# LED-mini-SHIM.net
KiCad netlist of a schematic drawn in EAGLE
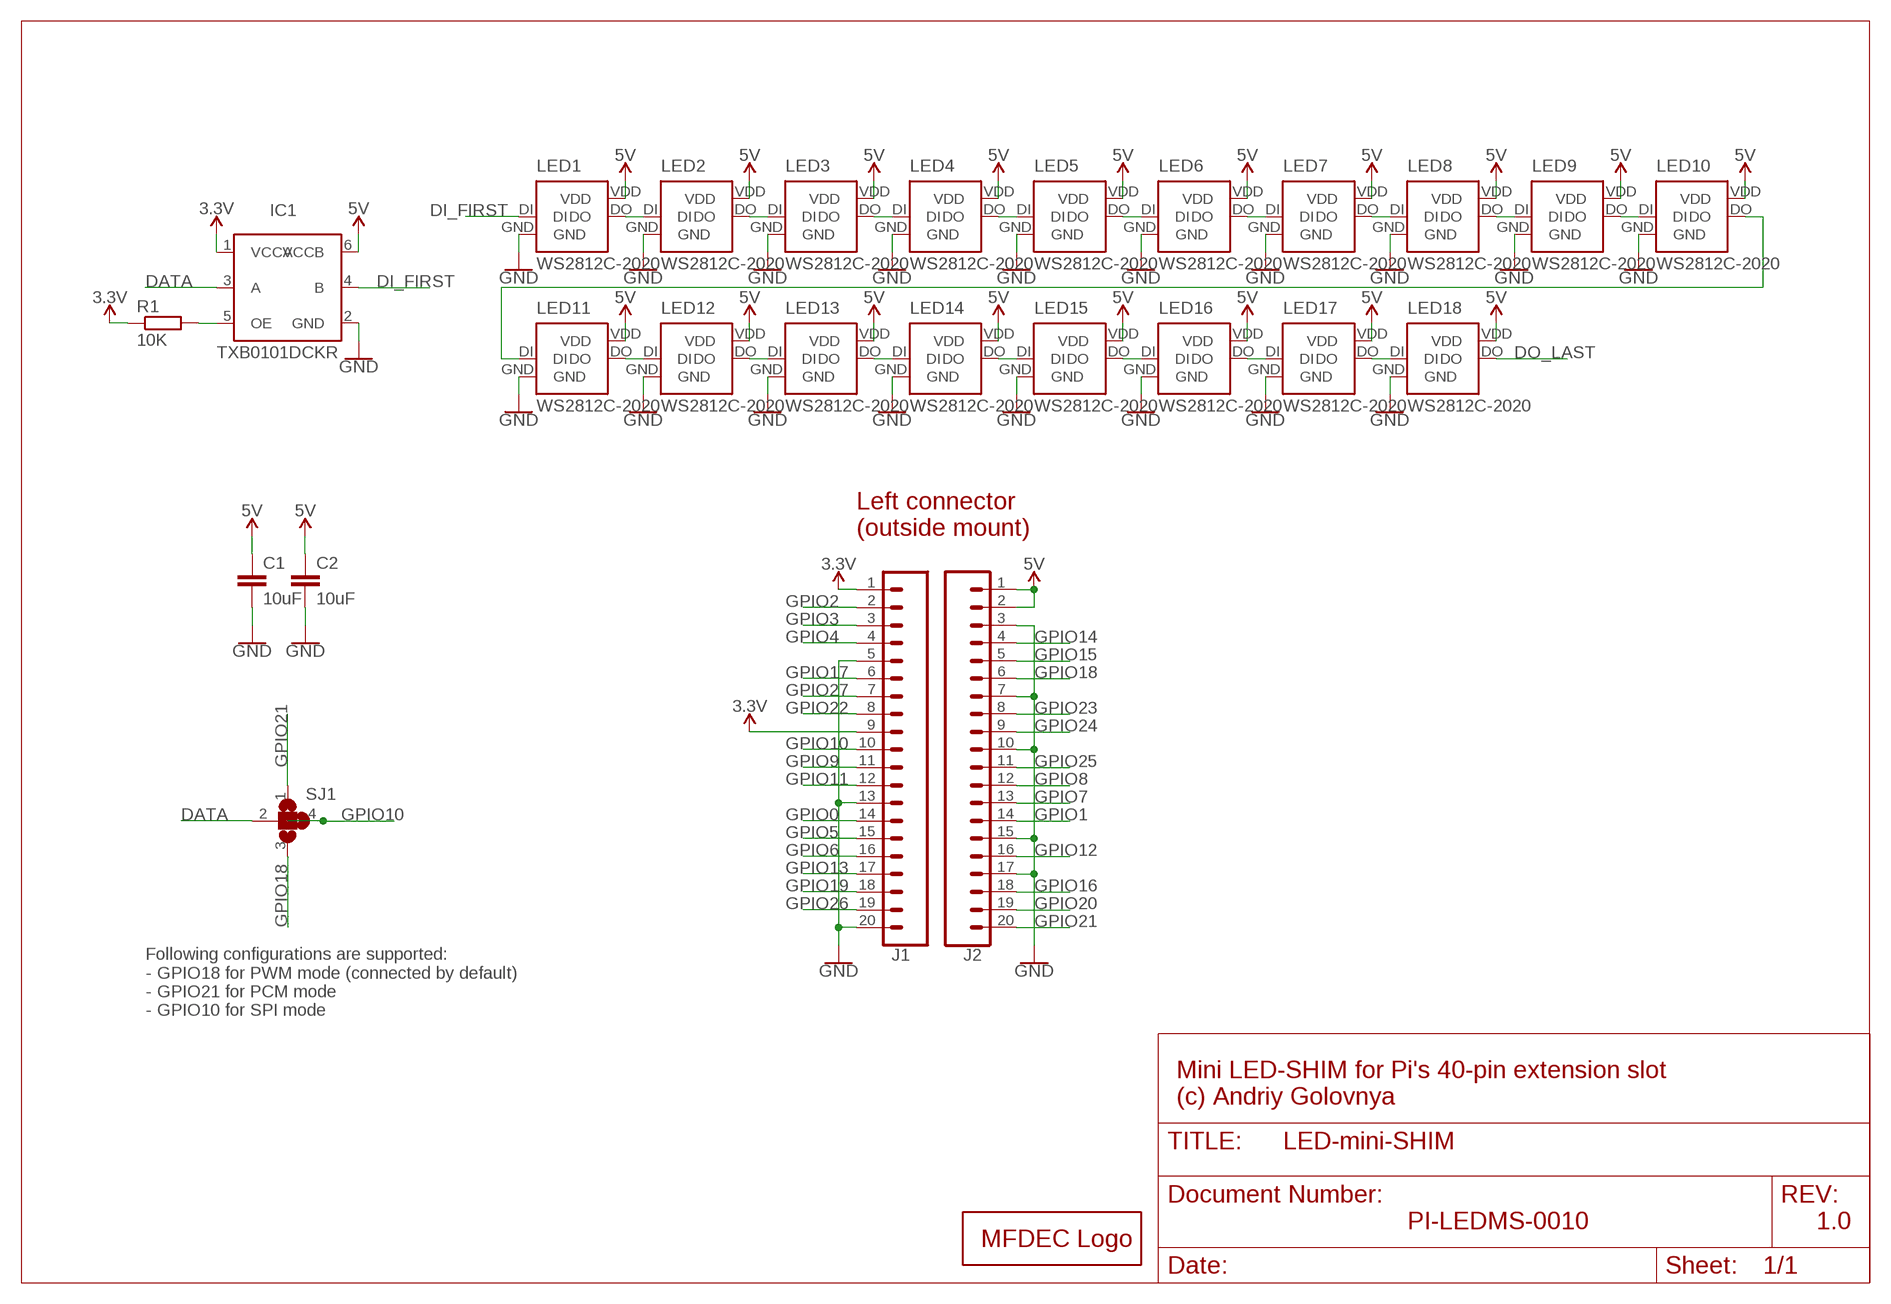
[diagram p0: schematic, sheet 1]

(export (version "E")
  (design (tool "Eeschema 10.0.6"))
  (components
    (comp (ref "C1")
      (value "10uF")
      (footprint "eagle-import:C0805")
      (libsource (lib "eagle-import") (part "C-EUC0805"))
    )
    (comp (ref "C2")
      (value "10uF")
      (footprint "eagle-import:C0805")
      (libsource (lib "eagle-import") (part "C-EUC0805"))
    )
    (comp (ref "IC1")
      (value "TXB0101DCKR")
      (footprint "eagle-import:SOT65P210X110-6N")
      (libsource (lib "eagle-import") (part "TXB0101DCKR"))
    )
    (comp (ref "J1")
      (value "CONN_20LOCK")
      (footprint "eagle-import:1X20_LOCK")
      (libsource (lib "eagle-import") (part "CONN_20LOCK"))
    )
    (comp (ref "J2")
      (value "CONN_20LOCK")
      (footprint "eagle-import:1X20_LOCK")
      (libsource (lib "eagle-import") (part "CONN_20LOCK"))
    )
    (comp (ref "LED1")
      (value "WS2812C-2020")
      (footprint "eagle-import:WS2812X-2020")
      (libsource (lib "eagle-import") (part "WS2812C-2020"))
    )
    (comp (ref "LED2")
      (value "WS2812C-2020")
      (footprint "eagle-import:WS2812X-2020")
      (libsource (lib "eagle-import") (part "WS2812C-2020"))
    )
    (comp (ref "LED3")
      (value "WS2812C-2020")
      (footprint "eagle-import:WS2812X-2020")
      (libsource (lib "eagle-import") (part "WS2812C-2020"))
    )
    (comp (ref "LED4")
      (value "WS2812C-2020")
      (footprint "eagle-import:WS2812X-2020")
      (libsource (lib "eagle-import") (part "WS2812C-2020"))
    )
    (comp (ref "LED5")
      (value "WS2812C-2020")
      (footprint "eagle-import:WS2812X-2020")
      (libsource (lib "eagle-import") (part "WS2812C-2020"))
    )
    (comp (ref "LED6")
      (value "WS2812C-2020")
      (footprint "eagle-import:WS2812X-2020")
      (libsource (lib "eagle-import") (part "WS2812C-2020"))
    )
    (comp (ref "LED7")
      (value "WS2812C-2020")
      (footprint "eagle-import:WS2812X-2020")
      (libsource (lib "eagle-import") (part "WS2812C-2020"))
    )
    (comp (ref "LED8")
      (value "WS2812C-2020")
      (footprint "eagle-import:WS2812X-2020")
      (libsource (lib "eagle-import") (part "WS2812C-2020"))
    )
    (comp (ref "LED9")
      (value "WS2812C-2020")
      (footprint "eagle-import:WS2812X-2020")
      (libsource (lib "eagle-import") (part "WS2812C-2020"))
    )
    (comp (ref "LED10")
      (value "WS2812C-2020")
      (footprint "eagle-import:WS2812X-2020")
      (libsource (lib "eagle-import") (part "WS2812C-2020"))
    )
    (comp (ref "LED11")
      (value "WS2812C-2020")
      (footprint "eagle-import:WS2812X-2020")
      (libsource (lib "eagle-import") (part "WS2812C-2020"))
    )
    (comp (ref "LED12")
      (value "WS2812C-2020")
      (footprint "eagle-import:WS2812X-2020")
      (libsource (lib "eagle-import") (part "WS2812C-2020"))
    )
    (comp (ref "LED13")
      (value "WS2812C-2020")
      (footprint "eagle-import:WS2812X-2020")
      (libsource (lib "eagle-import") (part "WS2812C-2020"))
    )
    (comp (ref "LED14")
      (value "WS2812C-2020")
      (footprint "eagle-import:WS2812X-2020")
      (libsource (lib "eagle-import") (part "WS2812C-2020"))
    )
    (comp (ref "LED15")
      (value "WS2812C-2020")
      (footprint "eagle-import:WS2812X-2020")
      (libsource (lib "eagle-import") (part "WS2812C-2020"))
    )
    (comp (ref "LED16")
      (value "WS2812C-2020")
      (footprint "eagle-import:WS2812X-2020")
      (libsource (lib "eagle-import") (part "WS2812C-2020"))
    )
    (comp (ref "LED17")
      (value "WS2812C-2020")
      (footprint "eagle-import:WS2812X-2020")
      (libsource (lib "eagle-import") (part "WS2812C-2020"))
    )
    (comp (ref "LED18")
      (value "WS2812C-2020")
      (footprint "eagle-import:WS2812X-2020")
      (libsource (lib "eagle-import") (part "WS2812C-2020"))
    )
    (comp (ref "LOGO1")
      (value "MFDECLOGO_L_10MM")
      (footprint "eagle-import:MFDEC_L_10MM")
      (libsource (lib "eagle-import") (part "MFDECLOGO_L_10MM"))
    )
    (comp (ref "R1")
      (value "10K")
      (footprint "eagle-import:R0402")
      (libsource (lib "eagle-import") (part "R-EU_R0402"))
    )
    (comp (ref "SJ1")
      (value "SJ3")
      (footprint "eagle-import:SJ_3")
      (libsource (lib "eagle-import") (part "SJ3"))
    )
  )
  (nets
    (net (code "1") (name "/DATA") (class "Default")
      (node (ref "IC1") (pin "3") (pinfunction "A_3") (pintype "bidirectional"))
      (node (ref "SJ1") (pin "2") (pinfunction "2_2") (pintype "passive"))
    )
    (net (code "2") (name "/DI_FIRST") (class "Default")
      (node (ref "IC1") (pin "4") (pinfunction "B_4") (pintype "bidirectional"))
      (node (ref "LED1") (pin "DI") (pinfunction "DI_DI") (pintype "input"))
    )
    (net (code "3") (name "/DO_LAST") (class "Default")
      (node (ref "LED18") (pin "DO") (pinfunction "DO_DO") (pintype "output"))
    )
    (net (code "4") (name "/GPIO0") (class "Default")
      (node (ref "J1") (pin "14") (pinfunction "14_14") (pintype "passive"))
    )
    (net (code "5") (name "/GPIO1") (class "Default")
      (node (ref "J2") (pin "14") (pinfunction "14_14") (pintype "passive"))
    )
    (net (code "6") (name "/GPIO2") (class "Default")
      (node (ref "J1") (pin "2") (pinfunction "2_2") (pintype "passive"))
    )
    (net (code "7") (name "/GPIO3") (class "Default")
      (node (ref "J1") (pin "3") (pinfunction "3_3") (pintype "passive"))
    )
    (net (code "8") (name "/GPIO4") (class "Default")
      (node (ref "J1") (pin "4") (pinfunction "4_4") (pintype "passive"))
    )
    (net (code "9") (name "/GPIO5") (class "Default")
      (node (ref "J1") (pin "15") (pinfunction "15_15") (pintype "passive"))
    )
    (net (code "10") (name "/GPIO6") (class "Default")
      (node (ref "J1") (pin "16") (pinfunction "16_16") (pintype "passive"))
    )
    (net (code "11") (name "/GPIO7") (class "Default")
      (node (ref "J2") (pin "13") (pinfunction "13_13") (pintype "passive"))
    )
    (net (code "12") (name "/GPIO8") (class "Default")
      (node (ref "J2") (pin "12") (pinfunction "12_12") (pintype "passive"))
    )
    (net (code "13") (name "/GPIO9") (class "Default")
      (node (ref "J1") (pin "11") (pinfunction "11_11") (pintype "passive"))
    )
    (net (code "14") (name "/GPIO10") (class "Default")
      (node (ref "J1") (pin "10") (pinfunction "10_10") (pintype "passive"))
      (node (ref "SJ1") (pin "4") (pinfunction "4_4") (pintype "passive"))
    )
    (net (code "15") (name "/GPIO11") (class "Default")
      (node (ref "J1") (pin "12") (pinfunction "12_12") (pintype "passive"))
    )
    (net (code "16") (name "/GPIO12") (class "Default")
      (node (ref "J2") (pin "16") (pinfunction "16_16") (pintype "passive"))
    )
    (net (code "17") (name "/GPIO13") (class "Default")
      (node (ref "J1") (pin "17") (pinfunction "17_17") (pintype "passive"))
    )
    (net (code "18") (name "/GPIO14") (class "Default")
      (node (ref "J2") (pin "4") (pinfunction "4_4") (pintype "passive"))
    )
    (net (code "19") (name "/GPIO15") (class "Default")
      (node (ref "J2") (pin "5") (pinfunction "5_5") (pintype "passive"))
    )
    (net (code "20") (name "/GPIO16") (class "Default")
      (node (ref "J2") (pin "18") (pinfunction "18_18") (pintype "passive"))
    )
    (net (code "21") (name "/GPIO17") (class "Default")
      (node (ref "J1") (pin "6") (pinfunction "6_6") (pintype "passive"))
    )
    (net (code "22") (name "/GPIO18") (class "Default")
      (node (ref "J2") (pin "6") (pinfunction "6_6") (pintype "passive"))
      (node (ref "SJ1") (pin "3") (pinfunction "3_3") (pintype "passive"))
    )
    (net (code "23") (name "/GPIO19") (class "Default")
      (node (ref "J1") (pin "18") (pinfunction "18_18") (pintype "passive"))
    )
    (net (code "24") (name "/GPIO20") (class "Default")
      (node (ref "J2") (pin "19") (pinfunction "19_19") (pintype "passive"))
    )
    (net (code "25") (name "/GPIO21") (class "Default")
      (node (ref "J2") (pin "20") (pinfunction "20_20") (pintype "passive"))
      (node (ref "SJ1") (pin "1") (pinfunction "1_1") (pintype "passive"))
    )
    (net (code "26") (name "/GPIO22") (class "Default")
      (node (ref "J1") (pin "8") (pinfunction "8_8") (pintype "passive"))
    )
    (net (code "27") (name "/GPIO23") (class "Default")
      (node (ref "J2") (pin "8") (pinfunction "8_8") (pintype "passive"))
    )
    (net (code "28") (name "/GPIO24") (class "Default")
      (node (ref "J2") (pin "9") (pinfunction "9_9") (pintype "passive"))
    )
    (net (code "29") (name "/GPIO25") (class "Default")
      (node (ref "J2") (pin "11") (pinfunction "11_11") (pintype "passive"))
    )
    (net (code "30") (name "/GPIO26") (class "Default")
      (node (ref "J1") (pin "19") (pinfunction "19_19") (pintype "passive"))
    )
    (net (code "31") (name "/GPIO27") (class "Default")
      (node (ref "J1") (pin "7") (pinfunction "7_7") (pintype "passive"))
    )
    (net (code "32") (name "3.3V") (class "Default")
      (node (ref "IC1") (pin "1") (pinfunction "VCCA_1") (pintype "power_in"))
      (node (ref "J1") (pin "1") (pinfunction "1_1") (pintype "passive"))
      (node (ref "J1") (pin "9") (pinfunction "9_9") (pintype "passive"))
      (node (ref "R1") (pin "1") (pinfunction "1_1") (pintype "passive"))
    )
    (net (code "33") (name "5V") (class "Default")
      (node (ref "C1") (pin "1") (pinfunction "1_1") (pintype "passive"))
      (node (ref "C2") (pin "1") (pinfunction "1_1") (pintype "passive"))
      (node (ref "IC1") (pin "6") (pinfunction "VCCB_6") (pintype "power_in"))
      (node (ref "J2") (pin "1") (pinfunction "1_1") (pintype "passive"))
      (node (ref "J2") (pin "2") (pinfunction "2_2") (pintype "passive"))
      (node (ref "LED1") (pin "VDD") (pinfunction "VDD_VDD") (pintype "power_in"))
      (node (ref "LED10") (pin "VDD") (pinfunction "VDD_VDD") (pintype "power_in"))
      (node (ref "LED11") (pin "VDD") (pinfunction "VDD_VDD") (pintype "power_in"))
      (node (ref "LED12") (pin "VDD") (pinfunction "VDD_VDD") (pintype "power_in"))
      (node (ref "LED13") (pin "VDD") (pinfunction "VDD_VDD") (pintype "power_in"))
      (node (ref "LED14") (pin "VDD") (pinfunction "VDD_VDD") (pintype "power_in"))
      (node (ref "LED15") (pin "VDD") (pinfunction "VDD_VDD") (pintype "power_in"))
      (node (ref "LED16") (pin "VDD") (pinfunction "VDD_VDD") (pintype "power_in"))
      (node (ref "LED17") (pin "VDD") (pinfunction "VDD_VDD") (pintype "power_in"))
      (node (ref "LED18") (pin "VDD") (pinfunction "VDD_VDD") (pintype "power_in"))
      (node (ref "LED2") (pin "VDD") (pinfunction "VDD_VDD") (pintype "power_in"))
      (node (ref "LED3") (pin "VDD") (pinfunction "VDD_VDD") (pintype "power_in"))
      (node (ref "LED4") (pin "VDD") (pinfunction "VDD_VDD") (pintype "power_in"))
      (node (ref "LED5") (pin "VDD") (pinfunction "VDD_VDD") (pintype "power_in"))
      (node (ref "LED6") (pin "VDD") (pinfunction "VDD_VDD") (pintype "power_in"))
      (node (ref "LED7") (pin "VDD") (pinfunction "VDD_VDD") (pintype "power_in"))
      (node (ref "LED8") (pin "VDD") (pinfunction "VDD_VDD") (pintype "power_in"))
      (node (ref "LED9") (pin "VDD") (pinfunction "VDD_VDD") (pintype "power_in"))
    )
    (net (code "34") (name "GND") (class "Default")
      (node (ref "C1") (pin "2") (pinfunction "2_2") (pintype "passive"))
      (node (ref "C2") (pin "2") (pinfunction "2_2") (pintype "passive"))
      (node (ref "IC1") (pin "2") (pinfunction "GND_2") (pintype "power_in"))
      (node (ref "J1") (pin "13") (pinfunction "13_13") (pintype "passive"))
      (node (ref "J1") (pin "20") (pinfunction "20_20") (pintype "passive"))
      (node (ref "J1") (pin "5") (pinfunction "5_5") (pintype "passive"))
      (node (ref "J2") (pin "10") (pinfunction "10_10") (pintype "passive"))
      (node (ref "J2") (pin "15") (pinfunction "15_15") (pintype "passive"))
      (node (ref "J2") (pin "17") (pinfunction "17_17") (pintype "passive"))
      (node (ref "J2") (pin "3") (pinfunction "3_3") (pintype "passive"))
      (node (ref "J2") (pin "7") (pinfunction "7_7") (pintype "passive"))
      (node (ref "LED1") (pin "GND") (pinfunction "GND_GND") (pintype "power_in"))
      (node (ref "LED10") (pin "GND") (pinfunction "GND_GND") (pintype "power_in"))
      (node (ref "LED11") (pin "GND") (pinfunction "GND_GND") (pintype "power_in"))
      (node (ref "LED12") (pin "GND") (pinfunction "GND_GND") (pintype "power_in"))
      (node (ref "LED13") (pin "GND") (pinfunction "GND_GND") (pintype "power_in"))
      (node (ref "LED14") (pin "GND") (pinfunction "GND_GND") (pintype "power_in"))
      (node (ref "LED15") (pin "GND") (pinfunction "GND_GND") (pintype "power_in"))
      (node (ref "LED16") (pin "GND") (pinfunction "GND_GND") (pintype "power_in"))
      (node (ref "LED17") (pin "GND") (pinfunction "GND_GND") (pintype "power_in"))
      (node (ref "LED18") (pin "GND") (pinfunction "GND_GND") (pintype "power_in"))
      (node (ref "LED2") (pin "GND") (pinfunction "GND_GND") (pintype "power_in"))
      (node (ref "LED3") (pin "GND") (pinfunction "GND_GND") (pintype "power_in"))
      (node (ref "LED4") (pin "GND") (pinfunction "GND_GND") (pintype "power_in"))
      (node (ref "LED5") (pin "GND") (pinfunction "GND_GND") (pintype "power_in"))
      (node (ref "LED6") (pin "GND") (pinfunction "GND_GND") (pintype "power_in"))
      (node (ref "LED7") (pin "GND") (pinfunction "GND_GND") (pintype "power_in"))
      (node (ref "LED8") (pin "GND") (pinfunction "GND_GND") (pintype "power_in"))
      (node (ref "LED9") (pin "GND") (pinfunction "GND_GND") (pintype "power_in"))
    )
    (net (code "35") (name "Net-(IC1-OE)") (class "Default")
      (node (ref "IC1") (pin "5") (pinfunction "OE_5") (pintype "input"))
      (node (ref "R1") (pin "2") (pinfunction "2_2") (pintype "passive"))
    )
    (net (code "36") (name "Net-(LED1-PadDO)") (class "Default")
      (node (ref "LED1") (pin "DO") (pinfunction "DO_DO") (pintype "output"))
      (node (ref "LED2") (pin "DI") (pinfunction "DI_DI") (pintype "input"))
    )
    (net (code "37") (name "Net-(LED2-PadDO)") (class "Default")
      (node (ref "LED2") (pin "DO") (pinfunction "DO_DO") (pintype "output"))
      (node (ref "LED3") (pin "DI") (pinfunction "DI_DI") (pintype "input"))
    )
    (net (code "38") (name "Net-(LED3-PadDO)") (class "Default")
      (node (ref "LED3") (pin "DO") (pinfunction "DO_DO") (pintype "output"))
      (node (ref "LED4") (pin "DI") (pinfunction "DI_DI") (pintype "input"))
    )
    (net (code "39") (name "Net-(LED4-PadDO)") (class "Default")
      (node (ref "LED4") (pin "DO") (pinfunction "DO_DO") (pintype "output"))
      (node (ref "LED5") (pin "DI") (pinfunction "DI_DI") (pintype "input"))
    )
    (net (code "40") (name "Net-(LED5-PadDO)") (class "Default")
      (node (ref "LED5") (pin "DO") (pinfunction "DO_DO") (pintype "output"))
      (node (ref "LED6") (pin "DI") (pinfunction "DI_DI") (pintype "input"))
    )
    (net (code "41") (name "Net-(LED6-PadDO)") (class "Default")
      (node (ref "LED6") (pin "DO") (pinfunction "DO_DO") (pintype "output"))
      (node (ref "LED7") (pin "DI") (pinfunction "DI_DI") (pintype "input"))
    )
    (net (code "42") (name "Net-(LED7-PadDO)") (class "Default")
      (node (ref "LED7") (pin "DO") (pinfunction "DO_DO") (pintype "output"))
      (node (ref "LED8") (pin "DI") (pinfunction "DI_DI") (pintype "input"))
    )
    (net (code "43") (name "Net-(LED8-PadDO)") (class "Default")
      (node (ref "LED8") (pin "DO") (pinfunction "DO_DO") (pintype "output"))
      (node (ref "LED9") (pin "DI") (pinfunction "DI_DI") (pintype "input"))
    )
    (net (code "44") (name "Net-(LED10-PadDI)") (class "Default")
      (node (ref "LED10") (pin "DI") (pinfunction "DI_DI") (pintype "input"))
      (node (ref "LED9") (pin "DO") (pinfunction "DO_DO") (pintype "output"))
    )
    (net (code "45") (name "Net-(LED10-PadDO)") (class "Default")
      (node (ref "LED10") (pin "DO") (pinfunction "DO_DO") (pintype "output"))
      (node (ref "LED11") (pin "DI") (pinfunction "DI_DI") (pintype "input"))
    )
    (net (code "46") (name "Net-(LED11-PadDO)") (class "Default")
      (node (ref "LED11") (pin "DO") (pinfunction "DO_DO") (pintype "output"))
      (node (ref "LED12") (pin "DI") (pinfunction "DI_DI") (pintype "input"))
    )
    (net (code "47") (name "Net-(LED12-PadDO)") (class "Default")
      (node (ref "LED12") (pin "DO") (pinfunction "DO_DO") (pintype "output"))
      (node (ref "LED13") (pin "DI") (pinfunction "DI_DI") (pintype "input"))
    )
    (net (code "48") (name "Net-(LED13-PadDO)") (class "Default")
      (node (ref "LED13") (pin "DO") (pinfunction "DO_DO") (pintype "output"))
      (node (ref "LED14") (pin "DI") (pinfunction "DI_DI") (pintype "input"))
    )
    (net (code "49") (name "Net-(LED14-PadDO)") (class "Default")
      (node (ref "LED14") (pin "DO") (pinfunction "DO_DO") (pintype "output"))
      (node (ref "LED15") (pin "DI") (pinfunction "DI_DI") (pintype "input"))
    )
    (net (code "50") (name "Net-(LED15-PadDO)") (class "Default")
      (node (ref "LED15") (pin "DO") (pinfunction "DO_DO") (pintype "output"))
      (node (ref "LED16") (pin "DI") (pinfunction "DI_DI") (pintype "input"))
    )
    (net (code "51") (name "Net-(LED16-PadDO)") (class "Default")
      (node (ref "LED16") (pin "DO") (pinfunction "DO_DO") (pintype "output"))
      (node (ref "LED17") (pin "DI") (pinfunction "DI_DI") (pintype "input"))
    )
    (net (code "52") (name "Net-(LED17-PadDO)") (class "Default")
      (node (ref "LED17") (pin "DO") (pinfunction "DO_DO") (pintype "output"))
      (node (ref "LED18") (pin "DI") (pinfunction "DI_DI") (pintype "input"))
    )
  )
)
